# Current_Sensor_cct.net
KiCad netlist of a schematic drawn in Altium Designer
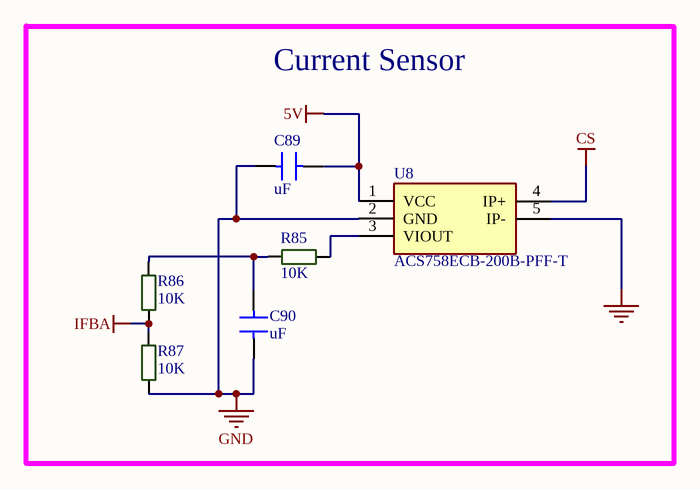
[diagram p0: Current_Sensor_cct.SchDoc]

(export (version "E")
  (design (tool "Eeschema 10.0.6"))
  (components
    (comp (ref "C89") (value "uF") (footprint "C-1206") (libsource (lib "PROJE") (part "C-1206")))
    (comp (ref "C90") (value "uF") (footprint "C-1206") (libsource (lib "PROJE") (part "C-1206")))
    (comp (ref "R85")
      (value "10K")
      (footprint "R-1206")
      (description "1206S4F1002T5E")
      (libsource (lib "PROJE") (part "R-1206_GS"))
    )
    (comp (ref "R86")
      (value "10K")
      (footprint "R-1206")
      (description "1206S4F1002T5E")
      (libsource (lib "PROJE") (part "R-1206_GS"))
    )
    (comp (ref "R87")
      (value "10K")
      (footprint "R-1206")
      (description "1206S4F1002T5E")
      (libsource (lib "PROJE") (part "R-1206_GS"))
    )
    (comp (ref "U8")
      (value "ACS758ECB-200B-PFF-T")
      (footprint "ACS756SCA-050B-PFF-T_2")
      (description "Undefined or Miscellaneous")
      (libsource (lib "PROJE") (part "ACS758ECB-200B-PFF-T"))
    )
  )
  (nets
    (net (code "1") (name "5V") (class "Default")
      (node (ref "C89") (pin "1") (pinfunction "1_1") (pintype "passive"))
      (node (ref "U8") (pin "1") (pinfunction "VCC_1") (pintype "passive"))
    )
    (net (code "2") (name "CS") (class "Default")
      (node (ref "U8") (pin "4") (pinfunction "IP+_4") (pintype "passive"))
    )
    (net (code "3") (name "GND") (class "Default")
      (node (ref "C89") (pin "2") (pinfunction "2_2") (pintype "passive"))
      (node (ref "C90") (pin "1") (pinfunction "1_1") (pintype "passive"))
      (node (ref "R87") (pin "2") (pinfunction "2_2") (pintype "passive"))
      (node (ref "U8") (pin "2") (pinfunction "GND_2") (pintype "passive"))
      (node (ref "U8") (pin "5") (pinfunction "IP-_5") (pintype "passive"))
    )
    (net (code "4") (name "IFBA") (class "Default")
      (node (ref "R86") (pin "2") (pinfunction "2_2") (pintype "passive"))
      (node (ref "R87") (pin "1") (pinfunction "1_1") (pintype "passive"))
    )
    (net (code "5") (name "Net-(C90-Pad2)") (class "Default")
      (node (ref "C90") (pin "2") (pinfunction "2_2") (pintype "passive"))
      (node (ref "R85") (pin "2") (pinfunction "2_2") (pintype "passive"))
      (node (ref "R86") (pin "1") (pinfunction "1_1") (pintype "passive"))
    )
    (net (code "6") (name "Net-(U8-VIOUT)") (class "Default")
      (node (ref "R85") (pin "1") (pinfunction "1_1") (pintype "passive"))
      (node (ref "U8") (pin "3") (pinfunction "VIOUT_3") (pintype "passive"))
    )
  )
)
